# Rectifire__PFC__Evaluation_Board.net
KiCad netlist of a schematic drawn in Altium Designer
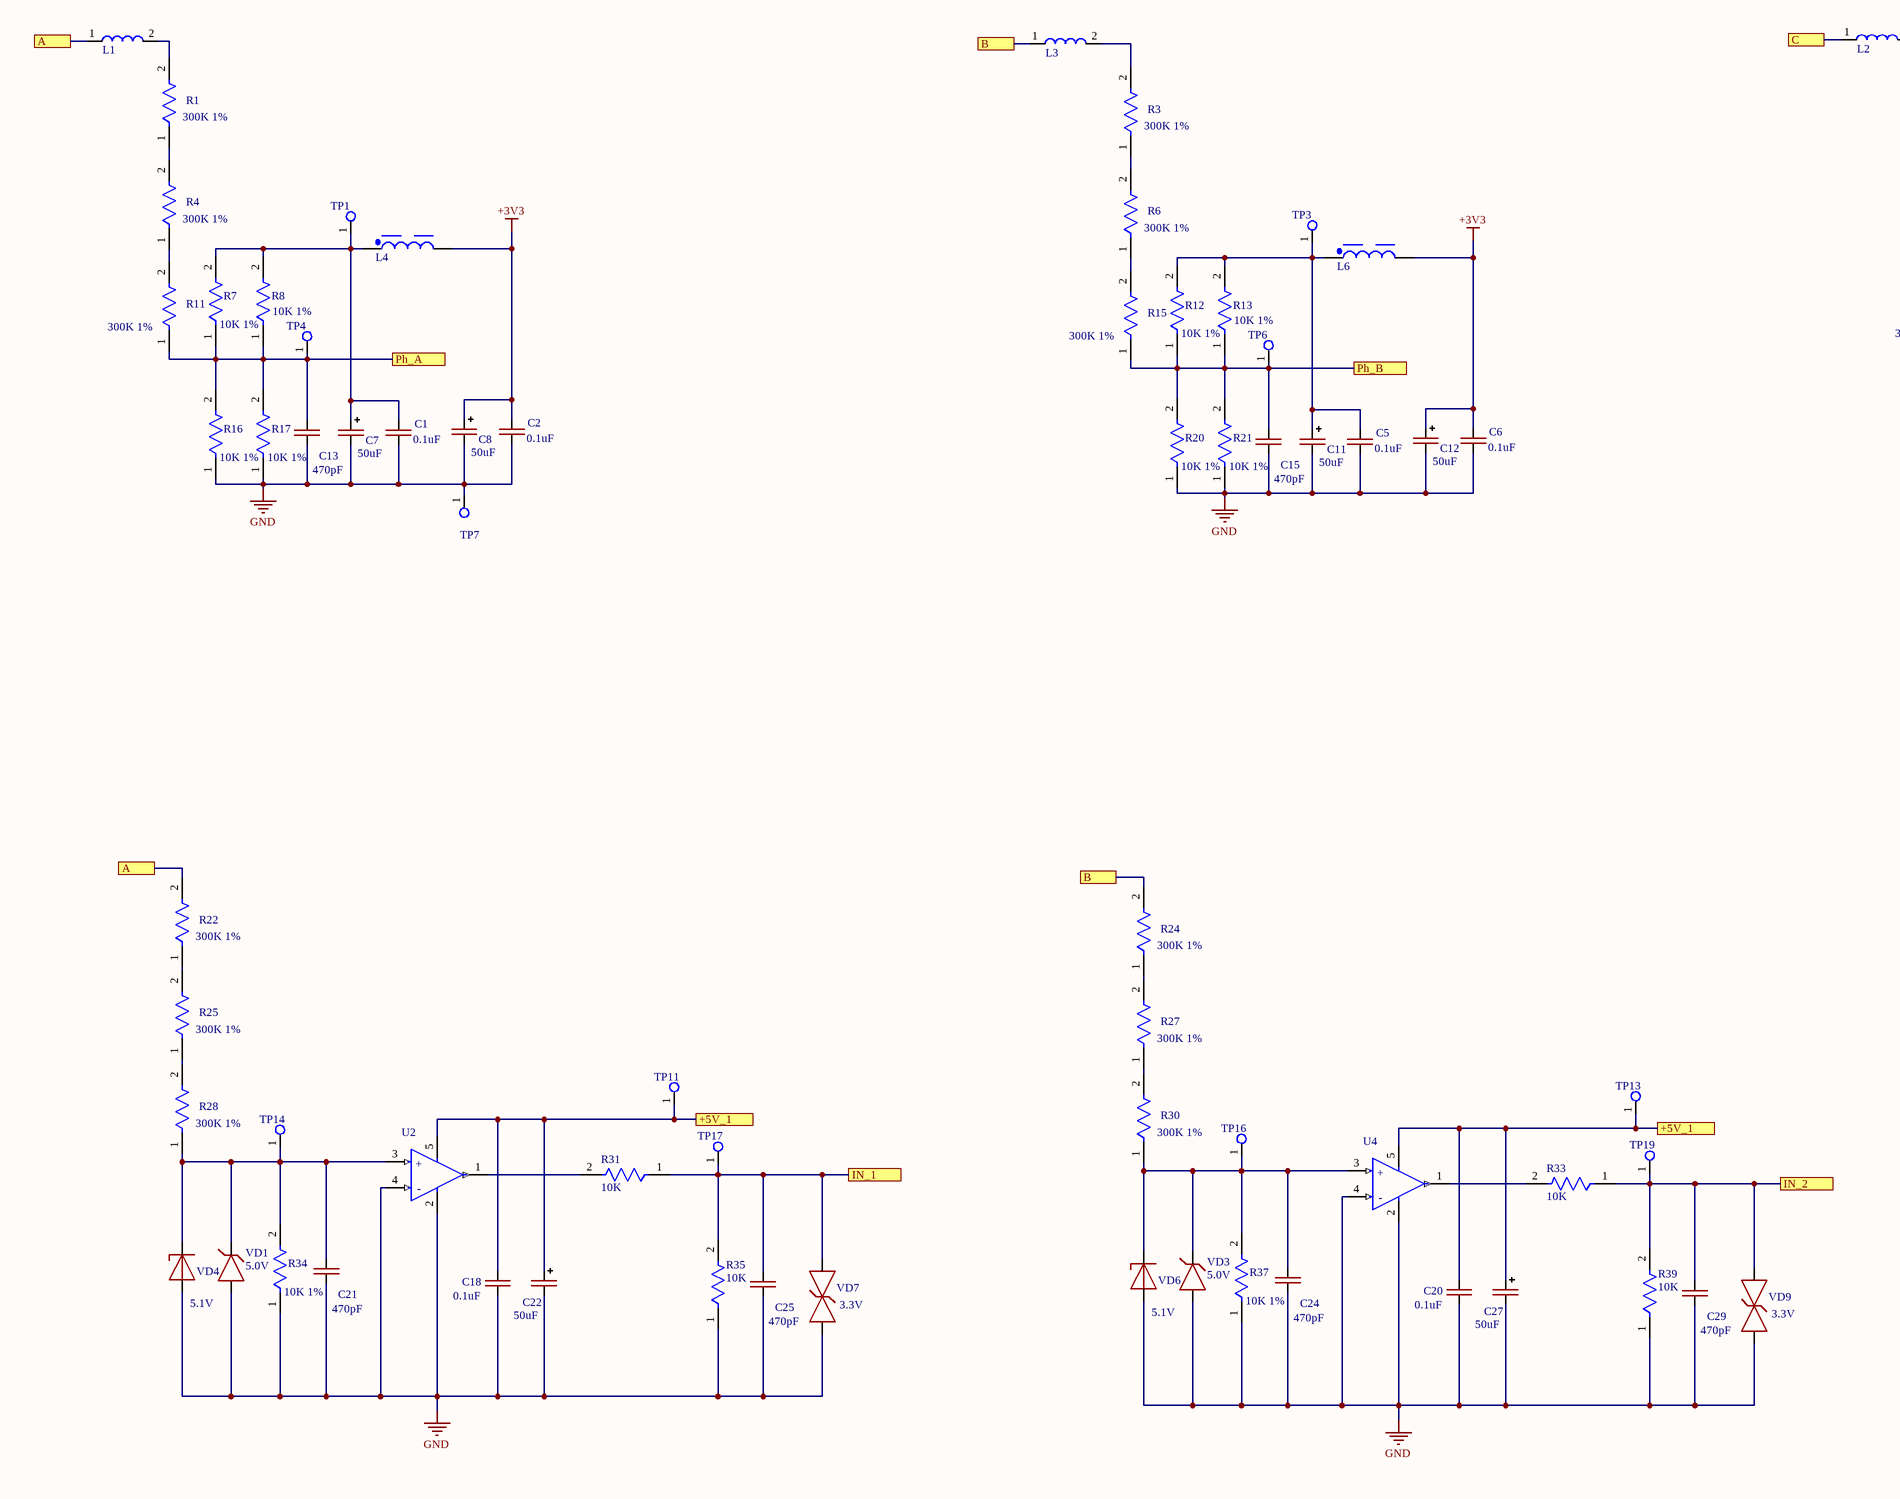
[diagram p0: Rectifire_(PFC)_Evaluation_Board.SchDoc, left]
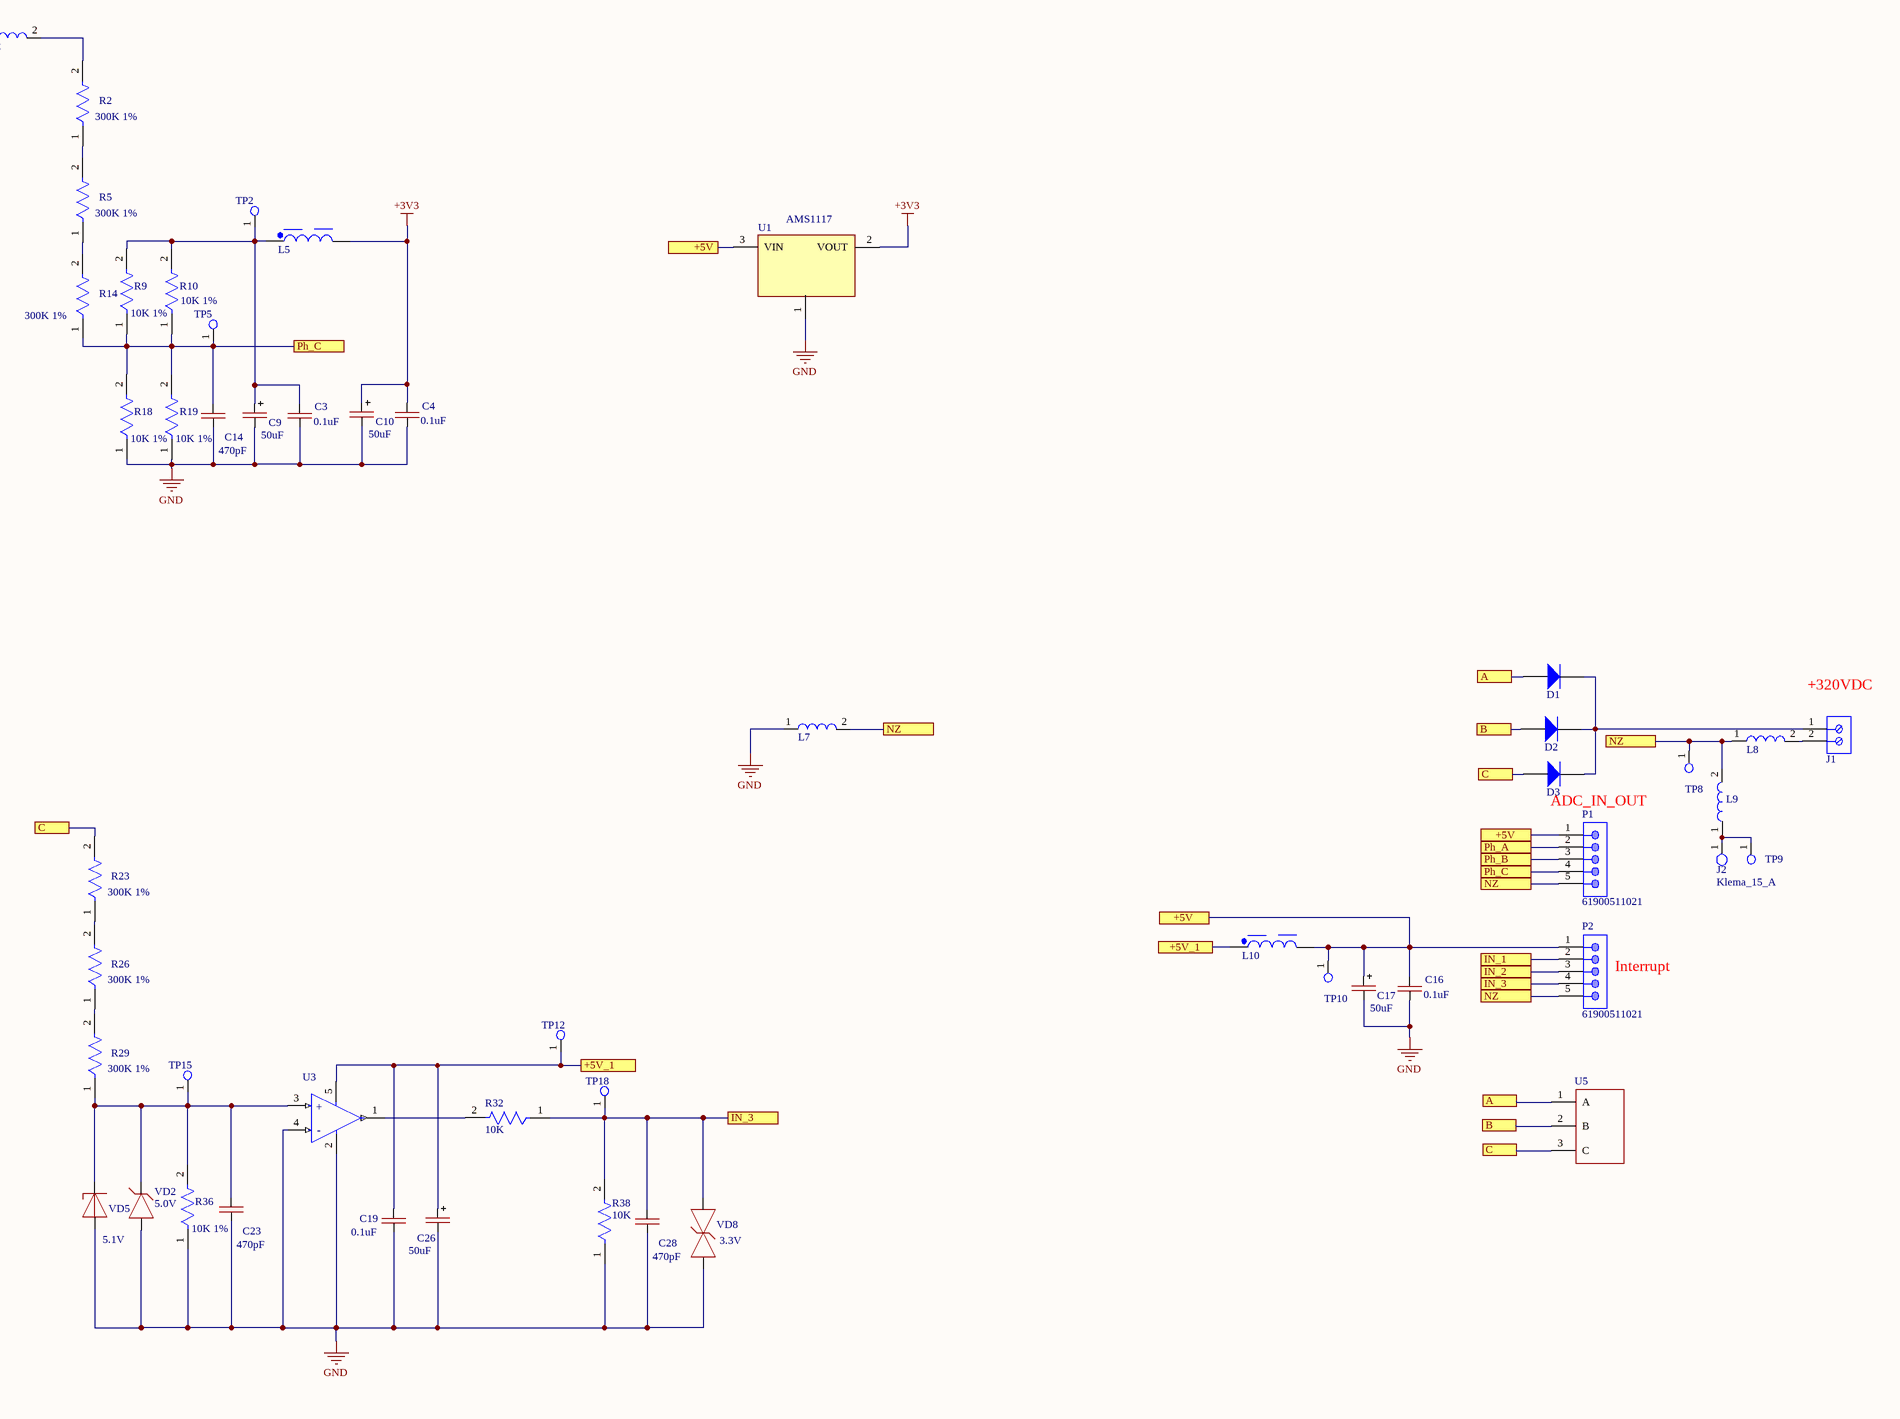
[diagram p1: Rectifire_(PFC)_Evaluation_Board.SchDoc, right]

(export (version "E")
  (design (tool "Eeschema 10.0.6"))
  (components
    (comp (ref "C1")
      (value "0.1uF")
      (footprint "CAP-0805")
      (libsource (lib "PASSIVE_COMPONENTS") (part "CAP-NON-POLAR"))
    )
    (comp (ref "C2")
      (value "0.1uF")
      (footprint "CAP-0805")
      (libsource (lib "PASSIVE_COMPONENTS") (part "CAP-NON-POLAR"))
    )
    (comp (ref "C3")
      (value "0.1uF")
      (footprint "CAP-0805")
      (libsource (lib "PASSIVE_COMPONENTS") (part "CAP-NON-POLAR"))
    )
    (comp (ref "C4")
      (value "0.1uF")
      (footprint "CAP-0805")
      (libsource (lib "PASSIVE_COMPONENTS") (part "CAP-NON-POLAR"))
    )
    (comp (ref "C5")
      (value "0.1uF")
      (footprint "CAP-0805")
      (libsource (lib "PASSIVE_COMPONENTS") (part "CAP-NON-POLAR"))
    )
    (comp (ref "C6")
      (value "0.1uF")
      (footprint "CAP-0805")
      (libsource (lib "PASSIVE_COMPONENTS") (part "CAP-NON-POLAR"))
    )
    (comp (ref "C7")
      (value "50uF")
      (footprint "CAP-TAN-D")
      (libsource (lib "PASSIVE_COMPONENTS") (part "CAP-POLAR"))
    )
    (comp (ref "C8")
      (value "50uF")
      (footprint "CAP-TAN-D")
      (libsource (lib "PASSIVE_COMPONENTS") (part "CAP-POLAR"))
    )
    (comp (ref "C9")
      (value "50uF")
      (footprint "CAP-TAN-D")
      (libsource (lib "PASSIVE_COMPONENTS") (part "CAP-POLAR"))
    )
    (comp (ref "C10")
      (value "50uF")
      (footprint "CAP-TAN-D")
      (libsource (lib "PASSIVE_COMPONENTS") (part "CAP-POLAR"))
    )
    (comp (ref "C11")
      (value "50uF")
      (footprint "CAP-TAN-D")
      (libsource (lib "PASSIVE_COMPONENTS") (part "CAP-POLAR"))
    )
    (comp (ref "C12")
      (value "50uF")
      (footprint "CAP-TAN-D")
      (libsource (lib "PASSIVE_COMPONENTS") (part "CAP-POLAR"))
    )
    (comp (ref "C13")
      (value "470pF")
      (footprint "CAP-0805")
      (libsource (lib "PASSIVE_COMPONENTS") (part "CAP-NON-POLAR"))
    )
    (comp (ref "C14")
      (value "470pF")
      (footprint "CAP-0805")
      (libsource (lib "PASSIVE_COMPONENTS") (part "CAP-NON-POLAR"))
    )
    (comp (ref "C15")
      (value "470pF")
      (footprint "CAP-0805")
      (libsource (lib "PASSIVE_COMPONENTS") (part "CAP-NON-POLAR"))
    )
    (comp (ref "C16")
      (value "0.1uF")
      (footprint "CAP-0805")
      (libsource (lib "PASSIVE_COMPONENTS") (part "CAP-NON-POLAR"))
    )
    (comp (ref "C17")
      (value "50uF")
      (footprint "CAP-TAN-D")
      (libsource (lib "PASSIVE_COMPONENTS") (part "CAP-POLAR"))
    )
    (comp (ref "C18")
      (value "0.1uF")
      (footprint "CAP-0805")
      (libsource (lib "PASSIVE_COMPONENTS") (part "CAP-NON-POLAR"))
    )
    (comp (ref "C19")
      (value "0.1uF")
      (footprint "CAP-0805")
      (libsource (lib "PASSIVE_COMPONENTS") (part "CAP-NON-POLAR"))
    )
    (comp (ref "C20")
      (value "0.1uF")
      (footprint "CAP-0805")
      (libsource (lib "PASSIVE_COMPONENTS") (part "CAP-NON-POLAR"))
    )
    (comp (ref "C21")
      (value "470pF")
      (footprint "CAP-0805")
      (libsource (lib "PASSIVE_COMPONENTS") (part "CAP-NON-POLAR"))
    )
    (comp (ref "C22")
      (value "50uF")
      (footprint "CAP-TAN-D")
      (libsource (lib "PASSIVE_COMPONENTS") (part "CAP-POLAR"))
    )
    (comp (ref "C23")
      (value "470pF")
      (footprint "CAP-0805")
      (libsource (lib "PASSIVE_COMPONENTS") (part "CAP-NON-POLAR"))
    )
    (comp (ref "C24")
      (value "470pF")
      (footprint "CAP-0805")
      (libsource (lib "PASSIVE_COMPONENTS") (part "CAP-NON-POLAR"))
    )
    (comp (ref "C25")
      (value "470pF")
      (footprint "CAP-0805")
      (libsource (lib "PASSIVE_COMPONENTS") (part "CAP-NON-POLAR"))
    )
    (comp (ref "C26")
      (value "50uF")
      (footprint "CAP-TAN-D")
      (libsource (lib "PASSIVE_COMPONENTS") (part "CAP-POLAR"))
    )
    (comp (ref "C27")
      (value "50uF")
      (footprint "CAP-TAN-D")
      (libsource (lib "PASSIVE_COMPONENTS") (part "CAP-POLAR"))
    )
    (comp (ref "C28")
      (value "470pF")
      (footprint "CAP-0805")
      (libsource (lib "PASSIVE_COMPONENTS") (part "CAP-NON-POLAR"))
    )
    (comp (ref "C29")
      (value "470pF")
      (footprint "CAP-0805")
      (libsource (lib "PASSIVE_COMPONENTS") (part "CAP-NON-POLAR"))
    )
    (comp (ref "D1")
      (value "FR-207")
      (footprint "FP-DO-201AD-MFG")
      (description "FR207")
      (libsource (lib "Diodes") (part "FR-207"))
    )
    (comp (ref "D2")
      (value "FR-207")
      (footprint "FP-DO-201AD-MFG")
      (description "FR207")
      (libsource (lib "Diodes") (part "FR-207"))
    )
    (comp (ref "D3")
      (value "FR-207")
      (footprint "FP-DO-201AD-MFG")
      (description "FR207")
      (libsource (lib "Diodes") (part "FR-207"))
    )
    (comp (ref "J1")
      (value "691101710002")
      (footprint "691101710002")
      (description "WR-TBL Series 101 Horizontal Entry Modular, THT, pitch 5mm, 2p")
      (fields (field (name "MANUFACTURER") "Wurth Elektronik"))
      (libsource (lib "Altium_WR-TBL (rev23f)") (part "691101710002"))
    )
    (comp (ref "J2")
      (value "Klema_15_A")
      (footprint "Connector_6mm")
      (libsource (lib "Connectors") (part "Klema_15_A"))
    )
    (comp (ref "L1") (value "Coil") (footprint "NR4030") (libsource (lib "Transformers") (part "Coil")))
    (comp (ref "L2") (value "Coil") (footprint "NR4030") (libsource (lib "Transformers") (part "Coil")))
    (comp (ref "L3") (value "Coil") (footprint "NR4030") (libsource (lib "Transformers") (part "Coil")))
    (comp (ref "L4")
      (value "12µH, 1.28A")
      (footprint "WE-PD2_4532")
      (description "WE-PD2 SMT Power Inductor, size 4532, 12µH, 1.28A, 0.21Ω")
      (fields
        (field (name "MANUFACTURER PART NUMBER") "744773112")
        (field (name "MANUFACTURER") "Wurth Elektronik")
      )
      (libsource (lib "WE-PD2 (rev22d)") (part "744773112"))
    )
    (comp (ref "L5")
      (value "12µH, 1.28A")
      (footprint "WE-PD2_4532")
      (description "WE-PD2 SMT Power Inductor, size 4532, 12µH, 1.28A, 0.21Ω")
      (fields
        (field (name "MANUFACTURER PART NUMBER") "744773112")
        (field (name "MANUFACTURER") "Wurth Elektronik")
      )
      (libsource (lib "WE-PD2 (rev22d)") (part "744773112"))
    )
    (comp (ref "L6")
      (value "12µH, 1.28A")
      (footprint "WE-PD2_4532")
      (description "WE-PD2 SMT Power Inductor, size 4532, 12µH, 1.28A, 0.21Ω")
      (fields
        (field (name "MANUFACTURER PART NUMBER") "744773112")
        (field (name "MANUFACTURER") "Wurth Elektronik")
      )
      (libsource (lib "WE-PD2 (rev22d)") (part "744773112"))
    )
    (comp (ref "L7") (value "Coil") (footprint "NR4030") (libsource (lib "Transformers") (part "Coil")))
    (comp (ref "L8") (value "Coil") (footprint "NR4030") (libsource (lib "Transformers") (part "Coil")))
    (comp (ref "L9") (value "Coil") (footprint "NR4030") (libsource (lib "Transformers") (part "Coil")))
    (comp (ref "L10")
      (value "12µH, 1.28A")
      (footprint "WE-PD2_4532")
      (description "WE-PD2 SMT Power Inductor, size 4532, 12µH, 1.28A, 0.21Ω")
      (fields
        (field (name "MANUFACTURER PART NUMBER") "744773112")
        (field (name "MANUFACTURER") "Wurth Elektronik")
      )
      (libsource (lib "WE-PD2 (rev22d)") (part "744773112"))
    )
    (comp (ref "P1")
      (value "61900511021")
      (footprint "61900511021")
      (description "WR-WTB THT Male Left Angled Bottom Locking Header, pitch 2.54mm, 5p")
      (fields (field (name "PUBLISHER") "Wurth Elektronik"))
      (libsource (lib "Altium_WR-WTB (rev20a)") (part "61900511021"))
    )
    (comp (ref "P2")
      (value "61900511021")
      (footprint "61900511021")
      (description "WR-WTB THT Male Left Angled Bottom Locking Header, pitch 2.54mm, 5p")
      (fields (field (name "PUBLISHER") "Wurth Elektronik"))
      (libsource (lib "Altium_WR-WTB (rev20a)") (part "61900511021"))
    )
    (comp (ref "R1")
      (value "300K 1%")
      (footprint "RES-1206")
      (description "300K")
      (libsource (lib "PASSIVE_COMPONENTS") (part "RES-CONST"))
    )
    (comp (ref "R2")
      (value "300K 1%")
      (footprint "RES-1206")
      (description "300K")
      (libsource (lib "PASSIVE_COMPONENTS") (part "RES-CONST"))
    )
    (comp (ref "R3")
      (value "300K 1%")
      (footprint "RES-1206")
      (description "300K")
      (libsource (lib "PASSIVE_COMPONENTS") (part "RES-CONST"))
    )
    (comp (ref "R4")
      (value "300K 1%")
      (footprint "RES-1206")
      (description "300K")
      (libsource (lib "PASSIVE_COMPONENTS") (part "RES-CONST"))
    )
    (comp (ref "R5")
      (value "300K 1%")
      (footprint "RES-1206")
      (description "300K")
      (libsource (lib "PASSIVE_COMPONENTS") (part "RES-CONST"))
    )
    (comp (ref "R6")
      (value "300K 1%")
      (footprint "RES-1206")
      (description "300K")
      (libsource (lib "PASSIVE_COMPONENTS") (part "RES-CONST"))
    )
    (comp (ref "R7")
      (value "10K 1%")
      (footprint "RES-1206")
      (libsource (lib "PASSIVE_COMPONENTS") (part "RES-CONST"))
    )
    (comp (ref "R8")
      (value "10K 1%")
      (footprint "RES-1206")
      (description "10K")
      (libsource (lib "PASSIVE_COMPONENTS") (part "RES-CONST"))
    )
    (comp (ref "R9")
      (value "10K 1%")
      (footprint "RES-1206")
      (libsource (lib "PASSIVE_COMPONENTS") (part "RES-CONST"))
    )
    (comp (ref "R10")
      (value "10K 1%")
      (footprint "RES-1206")
      (description "10K")
      (libsource (lib "PASSIVE_COMPONENTS") (part "RES-CONST"))
    )
    (comp (ref "R11")
      (value "300K 1%")
      (footprint "RES-1206")
      (description "300K")
      (libsource (lib "PASSIVE_COMPONENTS") (part "RES-CONST"))
    )
    (comp (ref "R12")
      (value "10K 1%")
      (footprint "RES-1206")
      (libsource (lib "PASSIVE_COMPONENTS") (part "RES-CONST"))
    )
    (comp (ref "R13")
      (value "10K 1%")
      (footprint "RES-1206")
      (description "10K")
      (libsource (lib "PASSIVE_COMPONENTS") (part "RES-CONST"))
    )
    (comp (ref "R14")
      (value "300K 1%")
      (footprint "RES-1206")
      (description "300K")
      (libsource (lib "PASSIVE_COMPONENTS") (part "RES-CONST"))
    )
    (comp (ref "R15")
      (value "300K 1%")
      (footprint "RES-1206")
      (description "300K")
      (libsource (lib "PASSIVE_COMPONENTS") (part "RES-CONST"))
    )
    (comp (ref "R16")
      (value "10K 1%")
      (footprint "RES-1206")
      (description "10K")
      (libsource (lib "PASSIVE_COMPONENTS") (part "RES-CONST"))
    )
    (comp (ref "R17")
      (value "10K 1%")
      (footprint "RES-1206")
      (description "10K")
      (libsource (lib "PASSIVE_COMPONENTS") (part "RES-CONST"))
    )
    (comp (ref "R18")
      (value "10K 1%")
      (footprint "RES-1206")
      (description "10K")
      (libsource (lib "PASSIVE_COMPONENTS") (part "RES-CONST"))
    )
    (comp (ref "R19")
      (value "10K 1%")
      (footprint "RES-1206")
      (description "10K")
      (libsource (lib "PASSIVE_COMPONENTS") (part "RES-CONST"))
    )
    (comp (ref "R20")
      (value "10K 1%")
      (footprint "RES-1206")
      (description "10K")
      (libsource (lib "PASSIVE_COMPONENTS") (part "RES-CONST"))
    )
    (comp (ref "R21")
      (value "10K 1%")
      (footprint "RES-1206")
      (description "10K")
      (libsource (lib "PASSIVE_COMPONENTS") (part "RES-CONST"))
    )
    (comp (ref "R22")
      (value "300K 1%")
      (footprint "RES-1206")
      (description "300K")
      (libsource (lib "PASSIVE_COMPONENTS") (part "RES-CONST"))
    )
    (comp (ref "R23")
      (value "300K 1%")
      (footprint "RES-1206")
      (description "300K")
      (libsource (lib "PASSIVE_COMPONENTS") (part "RES-CONST"))
    )
    (comp (ref "R24")
      (value "300K 1%")
      (footprint "RES-1206")
      (description "300K")
      (libsource (lib "PASSIVE_COMPONENTS") (part "RES-CONST"))
    )
    (comp (ref "R25")
      (value "300K 1%")
      (footprint "RES-1206")
      (description "300K")
      (libsource (lib "PASSIVE_COMPONENTS") (part "RES-CONST"))
    )
    (comp (ref "R26")
      (value "300K 1%")
      (footprint "RES-1206")
      (description "300K")
      (libsource (lib "PASSIVE_COMPONENTS") (part "RES-CONST"))
    )
    (comp (ref "R27")
      (value "300K 1%")
      (footprint "RES-1206")
      (description "300K")
      (libsource (lib "PASSIVE_COMPONENTS") (part "RES-CONST"))
    )
    (comp (ref "R28")
      (value "300K 1%")
      (footprint "RES-1206")
      (description "300K")
      (libsource (lib "PASSIVE_COMPONENTS") (part "RES-CONST"))
    )
    (comp (ref "R29")
      (value "300K 1%")
      (footprint "RES-1206")
      (description "300K")
      (libsource (lib "PASSIVE_COMPONENTS") (part "RES-CONST"))
    )
    (comp (ref "R30")
      (value "300K 1%")
      (footprint "RES-1206")
      (description "300K")
      (libsource (lib "PASSIVE_COMPONENTS") (part "RES-CONST"))
    )
    (comp (ref "R31")
      (value "10K")
      (footprint "RES-0805")
      (libsource (lib "PASSIVE_COMPONENTS") (part "RES-CONST"))
    )
    (comp (ref "R32")
      (value "10K")
      (footprint "RES-0805")
      (libsource (lib "PASSIVE_COMPONENTS") (part "RES-CONST"))
    )
    (comp (ref "R33")
      (value "10K")
      (footprint "RES-0805")
      (libsource (lib "PASSIVE_COMPONENTS") (part "RES-CONST"))
    )
    (comp (ref "R34")
      (value "10K 1%")
      (footprint "RES-1206")
      (libsource (lib "PASSIVE_COMPONENTS") (part "RES-CONST"))
    )
    (comp (ref "R35")
      (value "10K")
      (footprint "RES-0805")
      (libsource (lib "PASSIVE_COMPONENTS") (part "RES-CONST"))
    )
    (comp (ref "R36")
      (value "10K 1%")
      (footprint "RES-1206")
      (libsource (lib "PASSIVE_COMPONENTS") (part "RES-CONST"))
    )
    (comp (ref "R37")
      (value "10K 1%")
      (footprint "RES-1206")
      (libsource (lib "PASSIVE_COMPONENTS") (part "RES-CONST"))
    )
    (comp (ref "R38")
      (value "10K")
      (footprint "RES-0805")
      (libsource (lib "PASSIVE_COMPONENTS") (part "RES-CONST"))
    )
    (comp (ref "R39")
      (value "10K")
      (footprint "RES-0805")
      (libsource (lib "PASSIVE_COMPONENTS") (part "RES-CONST"))
    )
    (comp (ref "TP1")
      (value "Test_Point_PCB")
      (footprint "Test_Point")
      (description "Test_Point")
      (libsource (lib "Connectors") (part "TP_PCB?"))
    )
    (comp (ref "TP2")
      (value "Test_Point_PCB")
      (footprint "Test_Point")
      (description "Test_Point")
      (libsource (lib "Connectors") (part "TP_PCB?"))
    )
    (comp (ref "TP3")
      (value "Test_Point_PCB")
      (footprint "Test_Point")
      (description "Test_Point")
      (libsource (lib "Connectors") (part "TP_PCB?"))
    )
    (comp (ref "TP4")
      (value "Test_Point_PCB")
      (footprint "Test_Point")
      (description "Test_Point")
      (libsource (lib "Connectors") (part "TP_PCB?"))
    )
    (comp (ref "TP5")
      (value "Test_Point_PCB")
      (footprint "Test_Point")
      (description "Test_Point")
      (libsource (lib "Connectors") (part "TP_PCB?"))
    )
    (comp (ref "TP6")
      (value "Test_Point_PCB")
      (footprint "Test_Point")
      (description "Test_Point")
      (libsource (lib "Connectors") (part "TP_PCB?"))
    )
    (comp (ref "TP7")
      (value "Test_Point_PCB")
      (footprint "Pin_Test_Point(Pink)")
      (description "Test_Point")
      (libsource (lib "Connectors") (part "TP_PCB?"))
    )
    (comp (ref "TP8")
      (value "Test_Point_PCB")
      (footprint "Pin_Test_Point(Pink)")
      (description "Test_Point")
      (libsource (lib "Connectors") (part "TP_PCB?"))
    )
    (comp (ref "TP9")
      (value "Test_Point_PCB")
      (footprint "Pin_Test_Point(Pink)")
      (description "Test_Point")
      (libsource (lib "Connectors") (part "TP_PCB?"))
    )
    (comp (ref "TP10")
      (value "Test_Point_PCB")
      (footprint "Test_Point")
      (description "Test_Point")
      (libsource (lib "Connectors") (part "TP_PCB?"))
    )
    (comp (ref "TP11")
      (value "Test_Point_PCB")
      (footprint "Test_Point")
      (description "Test_Point")
      (libsource (lib "Connectors") (part "TP_PCB?"))
    )
    (comp (ref "TP12")
      (value "Test_Point_PCB")
      (footprint "Test_Point")
      (description "Test_Point")
      (libsource (lib "Connectors") (part "TP_PCB?"))
    )
    (comp (ref "TP13")
      (value "Test_Point_PCB")
      (footprint "Test_Point")
      (description "Test_Point")
      (libsource (lib "Connectors") (part "TP_PCB?"))
    )
    (comp (ref "TP14")
      (value "Test_Point_PCB")
      (footprint "Test_Point")
      (description "Test_Point")
      (libsource (lib "Connectors") (part "TP_PCB?"))
    )
    (comp (ref "TP15")
      (value "Test_Point_PCB")
      (footprint "Test_Point")
      (description "Test_Point")
      (libsource (lib "Connectors") (part "TP_PCB?"))
    )
    (comp (ref "TP16")
      (value "Test_Point_PCB")
      (footprint "Test_Point")
      (description "Test_Point")
      (libsource (lib "Connectors") (part "TP_PCB?"))
    )
    (comp (ref "TP17")
      (value "Test_Point_PCB")
      (footprint "Test_Point")
      (description "Test_Point")
      (libsource (lib "Connectors") (part "TP_PCB?"))
    )
    (comp (ref "TP18")
      (value "Test_Point_PCB")
      (footprint "Test_Point")
      (description "Test_Point")
      (libsource (lib "Connectors") (part "TP_PCB?"))
    )
    (comp (ref "TP19")
      (value "Test_Point_PCB")
      (footprint "Test_Point")
      (description "Test_Point")
      (libsource (lib "Connectors") (part "TP_PCB?"))
    )
    (comp (ref "U1")
      (value "AMS1117")
      (footprint "SOT-89")
      (libsource (lib "Integrated_Circuts") (part "AMS1117"))
    )
    (comp (ref "U2")
      (value "~")
      (footprint "SOT-23-5")
      (description "IC OPAMP GP 1 CIRCUIT SOT23-5")
      (fields (field (name "VOLTAGE") "6V"))
      (libsource (lib "Integrated_Circuts") (part "MCP6001T"))
    )
    (comp (ref "U3")
      (value "~")
      (footprint "SOT-23-5")
      (description "IC OPAMP GP 1 CIRCUIT SOT23-5")
      (fields (field (name "VOLTAGE") "6V"))
      (libsource (lib "Integrated_Circuts") (part "MCP6001T"))
    )
    (comp (ref "U4")
      (value "~")
      (footprint "SOT-23-5")
      (description "IC OPAMP GP 1 CIRCUIT SOT23-5")
      (fields (field (name "VOLTAGE") "6V"))
      (libsource (lib "Integrated_Circuts") (part "MCP6001T"))
    )
    (comp (ref "U5") (value "~") (footprint "MDS100") (libsource (lib "MDS100") (part "MDS100")))
    (comp (ref "VD1") (value "5.0V") (footprint "SOD-323") (libsource (lib "Diodes") (part "SMBJ15A")))
    (comp (ref "VD2") (value "5.0V") (footprint "SOD-323") (libsource (lib "Diodes") (part "SMBJ15A")))
    (comp (ref "VD3") (value "5.0V") (footprint "SOD-323") (libsource (lib "Diodes") (part "SMBJ15A")))
    (comp (ref "VD4") (value "5.1V") (footprint "DIOD-SOD123-2_V") (libsource (lib "Diodes") (part "ZENER")))
    (comp (ref "VD5") (value "5.1V") (footprint "DIOD-SOD123-2_V") (libsource (lib "Diodes") (part "ZENER")))
    (comp (ref "VD6") (value "5.1V") (footprint "DIOD-SOD123-2_V") (libsource (lib "Diodes") (part "ZENER")))
    (comp (ref "VD7") (value "3.3V") (footprint "DO-214AA") (libsource (lib "Diodes") (part "Suppressor")))
    (comp (ref "VD8") (value "3.3V") (footprint "DO-214AA") (libsource (lib "Diodes") (part "Suppressor")))
    (comp (ref "VD9") (value "3.3V") (footprint "DO-214AA") (libsource (lib "Diodes") (part "Suppressor")))
  )
  (nets
    (net (code "1") (name "+3V3") (class "Default")
      (node (ref "C10") (pin "1") (pinfunction "+_1") (pintype "passive"))
      (node (ref "C12") (pin "1") (pinfunction "+_1") (pintype "passive"))
      (node (ref "C2") (pin "2") (pinfunction "2_2") (pintype "passive"))
      (node (ref "C4") (pin "2") (pinfunction "2_2") (pintype "passive"))
      (node (ref "C6") (pin "2") (pinfunction "2_2") (pintype "passive"))
      (node (ref "C8") (pin "1") (pinfunction "+_1") (pintype "passive"))
      (node (ref "L4") (pin "2") (pinfunction "2_2") (pintype "passive"))
      (node (ref "L5") (pin "2") (pinfunction "2_2") (pintype "passive"))
      (node (ref "L6") (pin "2") (pinfunction "2_2") (pintype "passive"))
      (node (ref "U1") (pin "2") (pinfunction "VOUT_2") (pintype "passive"))
    )
    (net (code "2") (name "/+5V") (class "Default")
      (node (ref "C16") (pin "2") (pinfunction "2_2") (pintype "passive"))
      (node (ref "C17") (pin "1") (pinfunction "+_1") (pintype "passive"))
      (node (ref "L10") (pin "2") (pinfunction "2_2") (pintype "passive"))
      (node (ref "P1") (pin "1") (pinfunction "1_1") (pintype "passive"))
      (node (ref "P2") (pin "1") (pinfunction "1_1") (pintype "passive"))
      (node (ref "TP10") (pin "1") (pinfunction "G9_1") (pintype "passive"))
      (node (ref "U1") (pin "3") (pinfunction "VIN_3") (pintype "power_in"))
    )
    (net (code "3") (name "/+5V_1") (class "Default")
      (node (ref "C18") (pin "2") (pinfunction "2_2") (pintype "passive"))
      (node (ref "C19") (pin "2") (pinfunction "2_2") (pintype "passive"))
      (node (ref "C20") (pin "2") (pinfunction "2_2") (pintype "passive"))
      (node (ref "C22") (pin "1") (pinfunction "+_1") (pintype "passive"))
      (node (ref "C26") (pin "1") (pinfunction "+_1") (pintype "passive"))
      (node (ref "C27") (pin "1") (pinfunction "+_1") (pintype "passive"))
      (node (ref "L10") (pin "1") (pinfunction "1_1") (pintype "passive"))
      (node (ref "TP11") (pin "1") (pinfunction "G9_1") (pintype "passive"))
      (node (ref "TP12") (pin "1") (pinfunction "G9_1") (pintype "passive"))
      (node (ref "TP13") (pin "1") (pinfunction "G9_1") (pintype "passive"))
      (node (ref "U2") (pin "5") (pinfunction "VDD_5") (pintype "power_in"))
      (node (ref "U3") (pin "5") (pinfunction "VDD_5") (pintype "power_in"))
      (node (ref "U4") (pin "5") (pinfunction "VDD_5") (pintype "power_in"))
    )
    (net (code "4") (name "/A") (class "Default")
      (node (ref "D1") (pin "2") (pinfunction "A_2") (pintype "passive"))
      (node (ref "L1") (pin "1") (pinfunction "1_1") (pintype "passive"))
      (node (ref "R22") (pin "2") (pinfunction "2_2") (pintype "passive"))
      (node (ref "U5") (pin "1") (pinfunction "A_1") (pintype "tri_state"))
    )
    (net (code "5") (name "/B") (class "Default")
      (node (ref "D2") (pin "2") (pinfunction "A_2") (pintype "passive"))
      (node (ref "L3") (pin "1") (pinfunction "1_1") (pintype "passive"))
      (node (ref "R24") (pin "2") (pinfunction "2_2") (pintype "passive"))
      (node (ref "U5") (pin "2") (pinfunction "B_2") (pintype "tri_state"))
    )
    (net (code "6") (name "/C") (class "Default")
      (node (ref "D3") (pin "2") (pinfunction "A_2") (pintype "passive"))
      (node (ref "L2") (pin "1") (pinfunction "1_1") (pintype "passive"))
      (node (ref "R23") (pin "2") (pinfunction "2_2") (pintype "passive"))
      (node (ref "U5") (pin "3") (pinfunction "C_3") (pintype "tri_state"))
    )
    (net (code "7") (name "/IN_1") (class "Default")
      (node (ref "C25") (pin "2") (pinfunction "2_2") (pintype "passive"))
      (node (ref "P2") (pin "2") (pinfunction "2_2") (pintype "passive"))
      (node (ref "R31") (pin "1") (pinfunction "1_1") (pintype "passive"))
      (node (ref "R35") (pin "2") (pinfunction "2_2") (pintype "passive"))
      (node (ref "TP17") (pin "1") (pinfunction "G9_1") (pintype "passive"))
      (node (ref "VD7") (pin "2") (pinfunction "A_2") (pintype "passive"))
    )
    (net (code "8") (name "/IN_2") (class "Default")
      (node (ref "C29") (pin "2") (pinfunction "2_2") (pintype "passive"))
      (node (ref "P2") (pin "3") (pinfunction "3_3") (pintype "passive"))
      (node (ref "R33") (pin "1") (pinfunction "1_1") (pintype "passive"))
      (node (ref "R39") (pin "2") (pinfunction "2_2") (pintype "passive"))
      (node (ref "TP19") (pin "1") (pinfunction "G9_1") (pintype "passive"))
      (node (ref "VD9") (pin "2") (pinfunction "A_2") (pintype "passive"))
    )
    (net (code "9") (name "/IN_3") (class "Default")
      (node (ref "C28") (pin "2") (pinfunction "2_2") (pintype "passive"))
      (node (ref "P2") (pin "4") (pinfunction "4_4") (pintype "passive"))
      (node (ref "R32") (pin "1") (pinfunction "1_1") (pintype "passive"))
      (node (ref "R38") (pin "2") (pinfunction "2_2") (pintype "passive"))
      (node (ref "TP18") (pin "1") (pinfunction "G9_1") (pintype "passive"))
      (node (ref "VD8") (pin "2") (pinfunction "A_2") (pintype "passive"))
    )
    (net (code "10") (name "/NZ") (class "Default")
      (node (ref "L7") (pin "2") (pinfunction "2_2") (pintype "passive"))
      (node (ref "L8") (pin "1") (pinfunction "1_1") (pintype "passive"))
      (node (ref "L9") (pin "2") (pinfunction "2_2") (pintype "passive"))
      (node (ref "P1") (pin "5") (pinfunction "5_5") (pintype "passive"))
      (node (ref "P2") (pin "5") (pinfunction "5_5") (pintype "passive"))
      (node (ref "TP8") (pin "1") (pinfunction "G9_1") (pintype "passive"))
    )
    (net (code "11") (name "/Ph_A") (class "Default")
      (node (ref "C13") (pin "2") (pinfunction "2_2") (pintype "passive"))
      (node (ref "P1") (pin "2") (pinfunction "2_2") (pintype "passive"))
      (node (ref "R11") (pin "1") (pinfunction "1_1") (pintype "passive"))
      (node (ref "R16") (pin "2") (pinfunction "2_2") (pintype "passive"))
      (node (ref "R17") (pin "2") (pinfunction "2_2") (pintype "passive"))
      (node (ref "R7") (pin "1") (pinfunction "1_1") (pintype "passive"))
      (node (ref "R8") (pin "1") (pinfunction "1_1") (pintype "passive"))
      (node (ref "TP4") (pin "1") (pinfunction "G9_1") (pintype "passive"))
    )
    (net (code "12") (name "/Ph_B") (class "Default")
      (node (ref "C15") (pin "2") (pinfunction "2_2") (pintype "passive"))
      (node (ref "P1") (pin "3") (pinfunction "3_3") (pintype "passive"))
      (node (ref "R12") (pin "1") (pinfunction "1_1") (pintype "passive"))
      (node (ref "R13") (pin "1") (pinfunction "1_1") (pintype "passive"))
      (node (ref "R15") (pin "1") (pinfunction "1_1") (pintype "passive"))
      (node (ref "R20") (pin "2") (pinfunction "2_2") (pintype "passive"))
      (node (ref "R21") (pin "2") (pinfunction "2_2") (pintype "passive"))
      (node (ref "TP6") (pin "1") (pinfunction "G9_1") (pintype "passive"))
    )
    (net (code "13") (name "/Ph_C") (class "Default")
      (node (ref "C14") (pin "2") (pinfunction "2_2") (pintype "passive"))
      (node (ref "P1") (pin "4") (pinfunction "4_4") (pintype "passive"))
      (node (ref "R10") (pin "1") (pinfunction "1_1") (pintype "passive"))
      (node (ref "R14") (pin "1") (pinfunction "1_1") (pintype "passive"))
      (node (ref "R18") (pin "2") (pinfunction "2_2") (pintype "passive"))
      (node (ref "R19") (pin "2") (pinfunction "2_2") (pintype "passive"))
      (node (ref "R9") (pin "1") (pinfunction "1_1") (pintype "passive"))
      (node (ref "TP5") (pin "1") (pinfunction "G9_1") (pintype "passive"))
    )
    (net (code "14") (name "GND") (class "Default")
      (node (ref "C1") (pin "1") (pinfunction "1_1") (pintype "passive"))
      (node (ref "C10") (pin "2") (pinfunction "-_2") (pintype "passive"))
      (node (ref "C11") (pin "2") (pinfunction "-_2") (pintype "passive"))
      (node (ref "C12") (pin "2") (pinfunction "-_2") (pintype "passive"))
      (node (ref "C13") (pin "1") (pinfunction "1_1") (pintype "passive"))
      (node (ref "C14") (pin "1") (pinfunction "1_1") (pintype "passive"))
      (node (ref "C15") (pin "1") (pinfunction "1_1") (pintype "passive"))
      (node (ref "C16") (pin "1") (pinfunction "1_1") (pintype "passive"))
      (node (ref "C17") (pin "2") (pinfunction "-_2") (pintype "passive"))
      (node (ref "C18") (pin "1") (pinfunction "1_1") (pintype "passive"))
      (node (ref "C19") (pin "1") (pinfunction "1_1") (pintype "passive"))
      (node (ref "C2") (pin "1") (pinfunction "1_1") (pintype "passive"))
      (node (ref "C20") (pin "1") (pinfunction "1_1") (pintype "passive"))
      (node (ref "C21") (pin "1") (pinfunction "1_1") (pintype "passive"))
      (node (ref "C22") (pin "2") (pinfunction "-_2") (pintype "passive"))
      (node (ref "C23") (pin "1") (pinfunction "1_1") (pintype "passive"))
      (node (ref "C24") (pin "1") (pinfunction "1_1") (pintype "passive"))
      (node (ref "C25") (pin "1") (pinfunction "1_1") (pintype "passive"))
      (node (ref "C26") (pin "2") (pinfunction "-_2") (pintype "passive"))
      (node (ref "C27") (pin "2") (pinfunction "-_2") (pintype "passive"))
      (node (ref "C28") (pin "1") (pinfunction "1_1") (pintype "passive"))
      (node (ref "C29") (pin "1") (pinfunction "1_1") (pintype "passive"))
      (node (ref "C3") (pin "1") (pinfunction "1_1") (pintype "passive"))
      (node (ref "C4") (pin "1") (pinfunction "1_1") (pintype "passive"))
      (node (ref "C5") (pin "1") (pinfunction "1_1") (pintype "passive"))
      (node (ref "C6") (pin "1") (pinfunction "1_1") (pintype "passive"))
      (node (ref "C7") (pin "2") (pinfunction "-_2") (pintype "passive"))
      (node (ref "C8") (pin "2") (pinfunction "-_2") (pintype "passive"))
      (node (ref "C9") (pin "2") (pinfunction "-_2") (pintype "passive"))
      (node (ref "L7") (pin "1") (pinfunction "1_1") (pintype "passive"))
      (node (ref "R16") (pin "1") (pinfunction "1_1") (pintype "passive"))
      (node (ref "R17") (pin "1") (pinfunction "1_1") (pintype "passive"))
      (node (ref "R18") (pin "1") (pinfunction "1_1") (pintype "passive"))
      (node (ref "R19") (pin "1") (pinfunction "1_1") (pintype "passive"))
      (node (ref "R20") (pin "1") (pinfunction "1_1") (pintype "passive"))
      (node (ref "R21") (pin "1") (pinfunction "1_1") (pintype "passive"))
      (node (ref "R34") (pin "1") (pinfunction "1_1") (pintype "passive"))
      (node (ref "R35") (pin "1") (pinfunction "1_1") (pintype "passive"))
      (node (ref "R36") (pin "1") (pinfunction "1_1") (pintype "passive"))
      (node (ref "R37") (pin "1") (pinfunction "1_1") (pintype "passive"))
      (node (ref "R38") (pin "1") (pinfunction "1_1") (pintype "passive"))
      (node (ref "R39") (pin "1") (pinfunction "1_1") (pintype "passive"))
      (node (ref "TP7") (pin "1") (pinfunction "G9_1") (pintype "passive"))
      (node (ref "U1") (pin "1") (pinfunction "Ground_1") (pintype "power_in"))
      (node (ref "U2") (pin "2") (pinfunction "VSS_2") (pintype "power_in"))
      (node (ref "U2") (pin "4") (pinfunction "VIN-_4") (pintype "input"))
      (node (ref "U3") (pin "2") (pinfunction "VSS_2") (pintype "power_in"))
      (node (ref "U3") (pin "4") (pinfunction "VIN-_4") (pintype "input"))
      (node (ref "U4") (pin "2") (pinfunction "VSS_2") (pintype "power_in"))
      (node (ref "U4") (pin "4") (pinfunction "VIN-_4") (pintype "input"))
      (node (ref "VD1") (pin "1") (pinfunction "A_1") (pintype "passive"))
      (node (ref "VD2") (pin "1") (pinfunction "A_1") (pintype "passive"))
      (node (ref "VD3") (pin "1") (pinfunction "A_1") (pintype "passive"))
      (node (ref "VD4") (pin "2") (pinfunction "A_2") (pintype "passive"))
      (node (ref "VD5") (pin "2") (pinfunction "A_2") (pintype "passive"))
      (node (ref "VD6") (pin "2") (pinfunction "A_2") (pintype "passive"))
      (node (ref "VD7") (pin "1") (pinfunction "C_1") (pintype "passive"))
      (node (ref "VD8") (pin "1") (pinfunction "C_1") (pintype "passive"))
      (node (ref "VD9") (pin "1") (pinfunction "C_1") (pintype "passive"))
    )
    (net (code "15") (name "Net-(C7-+)") (class "Default")
      (node (ref "C1") (pin "2") (pinfunction "2_2") (pintype "passive"))
      (node (ref "C7") (pin "1") (pinfunction "+_1") (pintype "passive"))
      (node (ref "L4") (pin "1") (pinfunction "1_1") (pintype "passive"))
      (node (ref "R7") (pin "2") (pinfunction "2_2") (pintype "passive"))
      (node (ref "R8") (pin "2") (pinfunction "2_2") (pintype "passive"))
      (node (ref "TP1") (pin "1") (pinfunction "G9_1") (pintype "passive"))
    )
    (net (code "16") (name "Net-(C9-+)") (class "Default")
      (node (ref "C3") (pin "2") (pinfunction "2_2") (pintype "passive"))
      (node (ref "C9") (pin "1") (pinfunction "+_1") (pintype "passive"))
      (node (ref "L5") (pin "1") (pinfunction "1_1") (pintype "passive"))
      (node (ref "R10") (pin "2") (pinfunction "2_2") (pintype "passive"))
      (node (ref "R9") (pin "2") (pinfunction "2_2") (pintype "passive"))
      (node (ref "TP2") (pin "1") (pinfunction "G9_1") (pintype "passive"))
    )
    (net (code "17") (name "Net-(C11-+)") (class "Default")
      (node (ref "C11") (pin "1") (pinfunction "+_1") (pintype "passive"))
      (node (ref "C5") (pin "2") (pinfunction "2_2") (pintype "passive"))
      (node (ref "L6") (pin "1") (pinfunction "1_1") (pintype "passive"))
      (node (ref "R12") (pin "2") (pinfunction "2_2") (pintype "passive"))
      (node (ref "R13") (pin "2") (pinfunction "2_2") (pintype "passive"))
      (node (ref "TP3") (pin "1") (pinfunction "G9_1") (pintype "passive"))
    )
    (net (code "18") (name "Net-(D1-K)") (class "Default")
      (node (ref "D1") (pin "1") (pinfunction "K_1") (pintype "passive"))
      (node (ref "D2") (pin "1") (pinfunction "K_1") (pintype "passive"))
      (node (ref "D3") (pin "1") (pinfunction "K_1") (pintype "passive"))
      (node (ref "J1") (pin "1") (pinfunction "1_1") (pintype "passive"))
    )
    (net (code "19") (name "Net-(J1-Pad2)") (class "Default")
      (node (ref "J1") (pin "2") (pinfunction "2_2") (pintype "passive"))
      (node (ref "L8") (pin "2") (pinfunction "2_2") (pintype "passive"))
    )
    (net (code "20") (name "Net-(J2-0)") (class "Default")
      (node (ref "J2") (pin "1") (pinfunction "0_1") (pintype "passive"))
      (node (ref "L9") (pin "1") (pinfunction "1_1") (pintype "passive"))
      (node (ref "TP9") (pin "1") (pinfunction "G9_1") (pintype "passive"))
    )
    (net (code "21") (name "Net-(L1-Pad2)") (class "Default")
      (node (ref "L1") (pin "2") (pinfunction "2_2") (pintype "passive"))
      (node (ref "R1") (pin "2") (pinfunction "2_2") (pintype "passive"))
    )
    (net (code "22") (name "Net-(L2-Pad2)") (class "Default")
      (node (ref "L2") (pin "2") (pinfunction "2_2") (pintype "passive"))
      (node (ref "R2") (pin "2") (pinfunction "2_2") (pintype "passive"))
    )
    (net (code "23") (name "Net-(L3-Pad2)") (class "Default")
      (node (ref "L3") (pin "2") (pinfunction "2_2") (pintype "passive"))
      (node (ref "R3") (pin "2") (pinfunction "2_2") (pintype "passive"))
    )
    (net (code "24") (name "Net-(R1-Pad1)") (class "Default")
      (node (ref "R1") (pin "1") (pinfunction "1_1") (pintype "passive"))
      (node (ref "R4") (pin "2") (pinfunction "2_2") (pintype "passive"))
    )
    (net (code "25") (name "Net-(R2-Pad1)") (class "Default")
      (node (ref "R2") (pin "1") (pinfunction "1_1") (pintype "passive"))
      (node (ref "R5") (pin "2") (pinfunction "2_2") (pintype "passive"))
    )
    (net (code "26") (name "Net-(R3-Pad1)") (class "Default")
      (node (ref "R3") (pin "1") (pinfunction "1_1") (pintype "passive"))
      (node (ref "R6") (pin "2") (pinfunction "2_2") (pintype "passive"))
    )
    (net (code "27") (name "Net-(R11-Pad2)") (class "Default")
      (node (ref "R11") (pin "2") (pinfunction "2_2") (pintype "passive"))
      (node (ref "R4") (pin "1") (pinfunction "1_1") (pintype "passive"))
    )
    (net (code "28") (name "Net-(R14-Pad2)") (class "Default")
      (node (ref "R14") (pin "2") (pinfunction "2_2") (pintype "passive"))
      (node (ref "R5") (pin "1") (pinfunction "1_1") (pintype "passive"))
    )
    (net (code "29") (name "Net-(R15-Pad2)") (class "Default")
      (node (ref "R15") (pin "2") (pinfunction "2_2") (pintype "passive"))
      (node (ref "R6") (pin "1") (pinfunction "1_1") (pintype "passive"))
    )
    (net (code "30") (name "Net-(R22-Pad1)") (class "Default")
      (node (ref "R22") (pin "1") (pinfunction "1_1") (pintype "passive"))
      (node (ref "R25") (pin "2") (pinfunction "2_2") (pintype "passive"))
    )
    (net (code "31") (name "Net-(R23-Pad1)") (class "Default")
      (node (ref "R23") (pin "1") (pinfunction "1_1") (pintype "passive"))
      (node (ref "R26") (pin "2") (pinfunction "2_2") (pintype "passive"))
    )
    (net (code "32") (name "Net-(R24-Pad1)") (class "Default")
      (node (ref "R24") (pin "1") (pinfunction "1_1") (pintype "passive"))
      (node (ref "R27") (pin "2") (pinfunction "2_2") (pintype "passive"))
    )
    (net (code "33") (name "Net-(R25-Pad1)") (class "Default")
      (node (ref "R25") (pin "1") (pinfunction "1_1") (pintype "passive"))
      (node (ref "R28") (pin "2") (pinfunction "2_2") (pintype "passive"))
    )
    (net (code "34") (name "Net-(R26-Pad1)") (class "Default")
      (node (ref "R26") (pin "1") (pinfunction "1_1") (pintype "passive"))
      (node (ref "R29") (pin "2") (pinfunction "2_2") (pintype "passive"))
    )
    (net (code "35") (name "Net-(R27-Pad1)") (class "Default")
      (node (ref "R27") (pin "1") (pinfunction "1_1") (pintype "passive"))
      (node (ref "R30") (pin "2") (pinfunction "2_2") (pintype "passive"))
    )
    (net (code "36") (name "Net-(TP14-G9)") (class "Default")
      (node (ref "C21") (pin "2") (pinfunction "2_2") (pintype "passive"))
      (node (ref "R28") (pin "1") (pinfunction "1_1") (pintype "passive"))
      (node (ref "R34") (pin "2") (pinfunction "2_2") (pintype "passive"))
      (node (ref "TP14") (pin "1") (pinfunction "G9_1") (pintype "passive"))
      (node (ref "U2") (pin "3") (pinfunction "VIN+_3") (pintype "input"))
      (node (ref "VD1") (pin "2") (pinfunction "C_2") (pintype "passive"))
      (node (ref "VD4") (pin "1") (pinfunction "C_1") (pintype "passive"))
    )
    (net (code "37") (name "Net-(TP15-G9)") (class "Default")
      (node (ref "C23") (pin "2") (pinfunction "2_2") (pintype "passive"))
      (node (ref "R29") (pin "1") (pinfunction "1_1") (pintype "passive"))
      (node (ref "R36") (pin "2") (pinfunction "2_2") (pintype "passive"))
      (node (ref "TP15") (pin "1") (pinfunction "G9_1") (pintype "passive"))
      (node (ref "U3") (pin "3") (pinfunction "VIN+_3") (pintype "input"))
      (node (ref "VD2") (pin "2") (pinfunction "C_2") (pintype "passive"))
      (node (ref "VD5") (pin "1") (pinfunction "C_1") (pintype "passive"))
    )
    (net (code "38") (name "Net-(TP16-G9)") (class "Default")
      (node (ref "C24") (pin "2") (pinfunction "2_2") (pintype "passive"))
      (node (ref "R30") (pin "1") (pinfunction "1_1") (pintype "passive"))
      (node (ref "R37") (pin "2") (pinfunction "2_2") (pintype "passive"))
      (node (ref "TP16") (pin "1") (pinfunction "G9_1") (pintype "passive"))
      (node (ref "U4") (pin "3") (pinfunction "VIN+_3") (pintype "input"))
      (node (ref "VD3") (pin "2") (pinfunction "C_2") (pintype "passive"))
      (node (ref "VD6") (pin "1") (pinfunction "C_1") (pintype "passive"))
    )
    (net (code "39") (name "Net-(U2-VOUT)") (class "Default")
      (node (ref "R31") (pin "2") (pinfunction "2_2") (pintype "passive"))
      (node (ref "U2") (pin "1") (pinfunction "VOUT_1") (pintype "output"))
    )
    (net (code "40") (name "Net-(U3-VOUT)") (class "Default")
      (node (ref "R32") (pin "2") (pinfunction "2_2") (pintype "passive"))
      (node (ref "U3") (pin "1") (pinfunction "VOUT_1") (pintype "output"))
    )
    (net (code "41") (name "Net-(U4-VOUT)") (class "Default")
      (node (ref "R33") (pin "2") (pinfunction "2_2") (pintype "passive"))
      (node (ref "U4") (pin "1") (pinfunction "VOUT_1") (pintype "output"))
    )
  )
)
